# Pico2_W5_V1_0_20240830.net
KiCad netlist of a schematic drawn in EAGLE
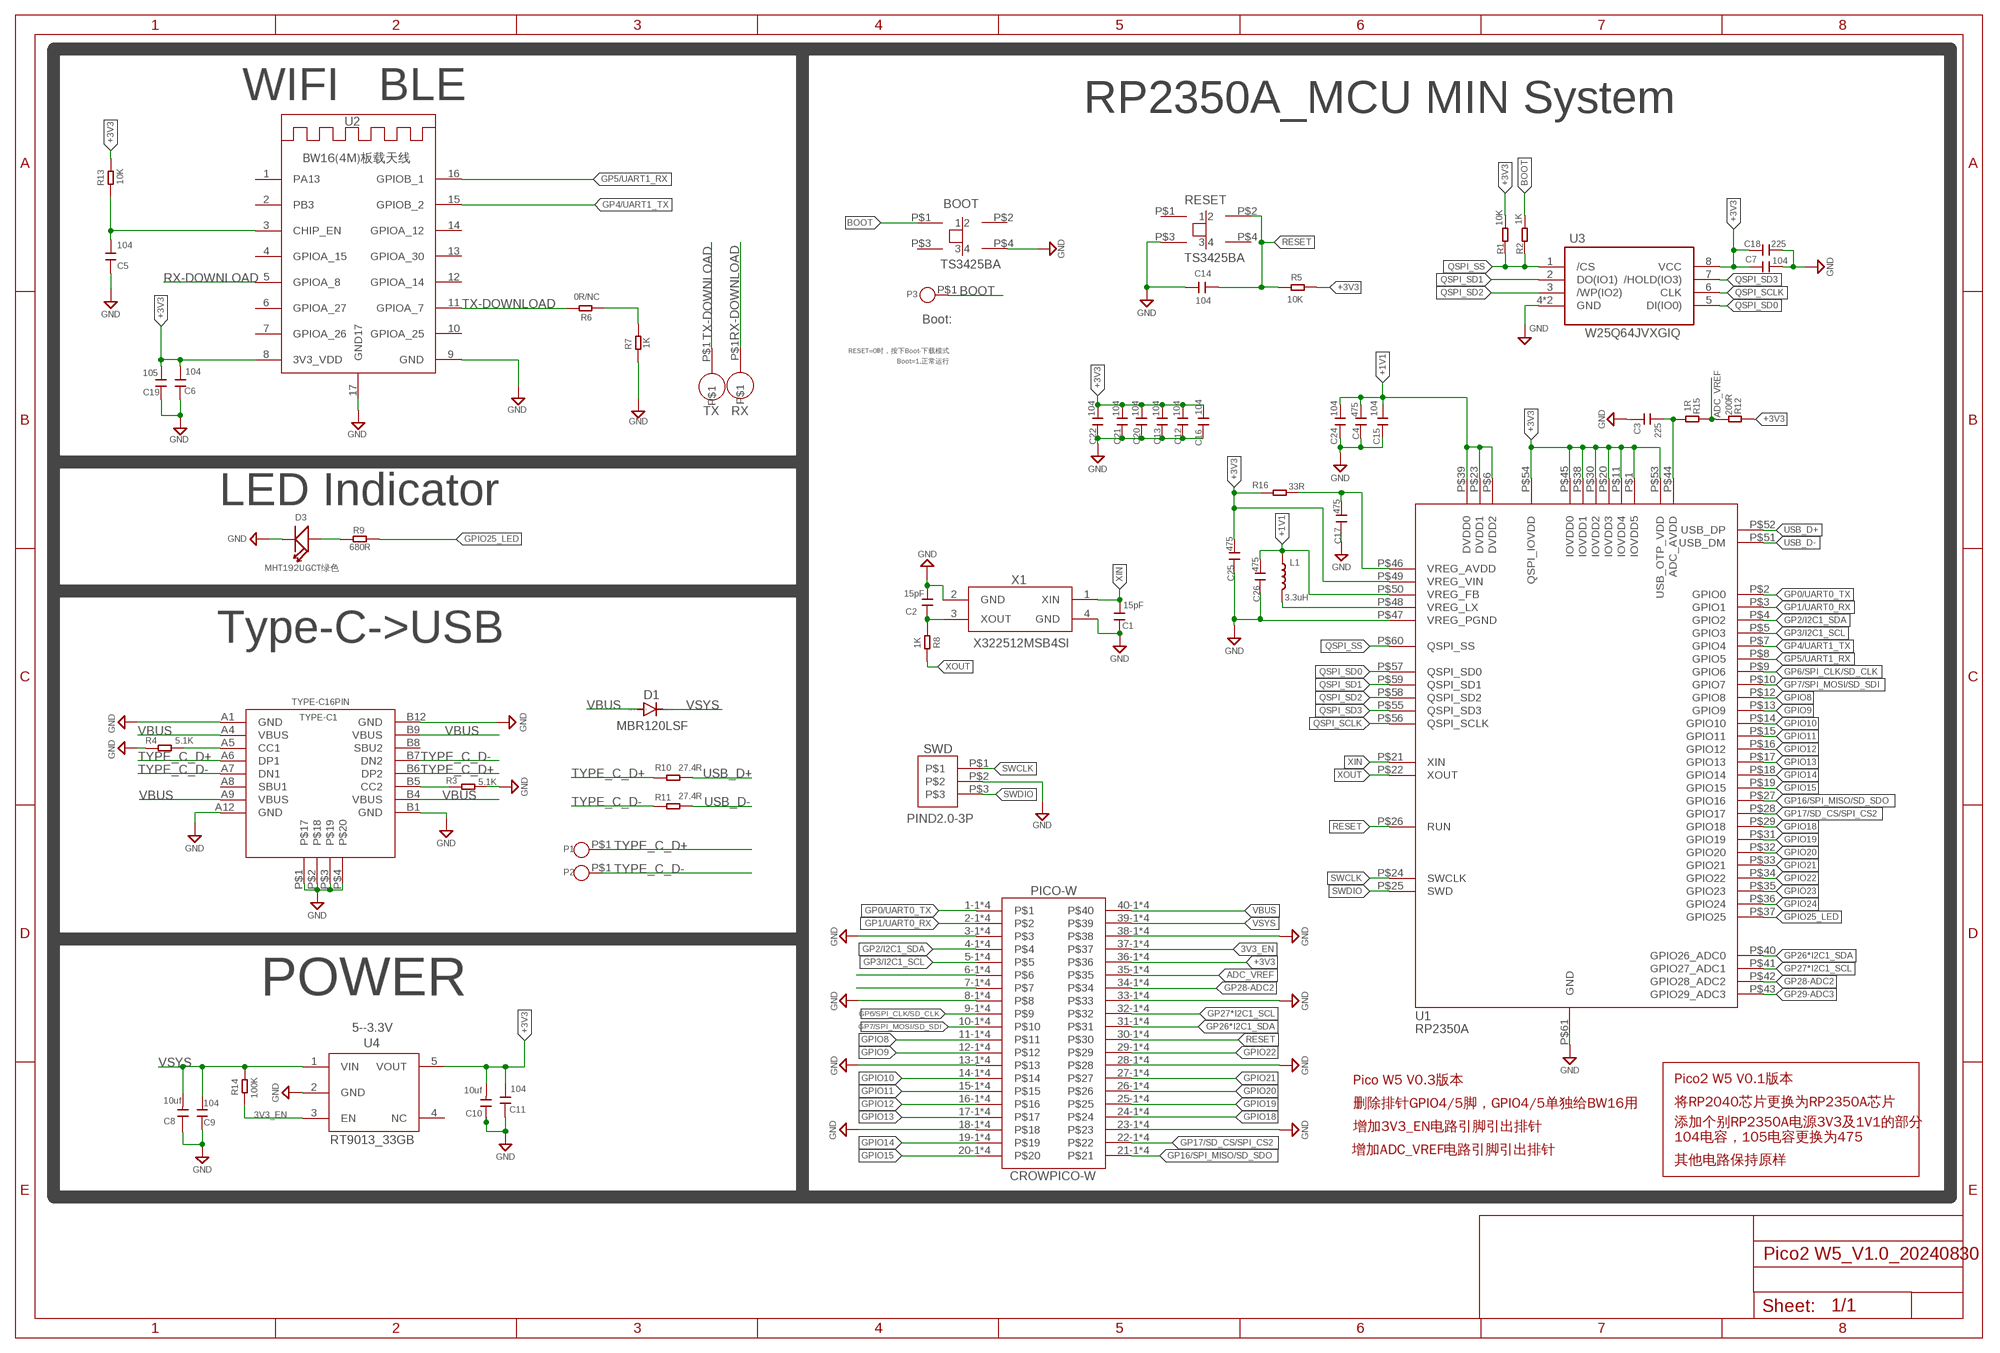
[diagram p0: schematic, sheet 1]

(export (version "E")
  (design (tool "Eeschema 10.0.6"))
  (components
    (comp (ref "BOOT")
      (value "TS3425BA")
      (footprint "eagle-import:SMD_KEY4.2_3._.2.5")
      (libsource (lib "eagle-import") (part "KEY"))
    )
    (comp (ref "C1")
      (value "15pF")
      (footprint "eagle-import:0201_W")
      (libsource (lib "eagle-import") (part "C0201"))
    )
    (comp (ref "C2")
      (value "15pF")
      (footprint "eagle-import:0201_W")
      (libsource (lib "eagle-import") (part "C0201"))
    )
    (comp (ref "C3")
      (value "225")
      (footprint "eagle-import:0201_W")
      (libsource (lib "eagle-import") (part "C0201"))
    )
    (comp (ref "C4")
      (value "475")
      (footprint "eagle-import:0201_W")
      (libsource (lib "eagle-import") (part "C0201"))
    )
    (comp (ref "C5")
      (value "104")
      (footprint "eagle-import:0201_W")
      (libsource (lib "eagle-import") (part "C0201"))
    )
    (comp (ref "C6")
      (value "104")
      (footprint "eagle-import:0201_W")
      (libsource (lib "eagle-import") (part "C0201"))
    )
    (comp (ref "C7")
      (value "104")
      (footprint "eagle-import:0201_W")
      (libsource (lib "eagle-import") (part "C0201"))
    )
    (comp (ref "C8")
      (value "10uf")
      (footprint "eagle-import:0402")
      (libsource (lib "eagle-import") (part "C0402"))
    )
    (comp (ref "C9")
      (value "104")
      (footprint "eagle-import:0201_W")
      (libsource (lib "eagle-import") (part "WGH_C0402"))
    )
    (comp (ref "C10")
      (value "10uf")
      (footprint "eagle-import:0402")
      (libsource (lib "eagle-import") (part "C0402"))
    )
    (comp (ref "C11")
      (value "104")
      (footprint "eagle-import:0201_W")
      (libsource (lib "eagle-import") (part "WGH_C0402"))
    )
    (comp (ref "C12")
      (value "104")
      (footprint "eagle-import:0201_W")
      (libsource (lib "eagle-import") (part "C0201"))
    )
    (comp (ref "C13")
      (value "104")
      (footprint "eagle-import:0201_W")
      (libsource (lib "eagle-import") (part "C0201"))
    )
    (comp (ref "C14")
      (value "104")
      (footprint "eagle-import:0201_W")
      (libsource (lib "eagle-import") (part "WGH_C0402"))
    )
    (comp (ref "C15")
      (value "104")
      (footprint "eagle-import:0201_W")
      (libsource (lib "eagle-import") (part "C0201"))
    )
    (comp (ref "C16")
      (value "104")
      (footprint "eagle-import:0201_W")
      (libsource (lib "eagle-import") (part "C0201"))
    )
    (comp (ref "C17")
      (value "475")
      (footprint "eagle-import:0201_W")
      (libsource (lib "eagle-import") (part "C0201"))
    )
    (comp (ref "C18")
      (value "225")
      (footprint "eagle-import:0201_W")
      (libsource (lib "eagle-import") (part "C0201"))
    )
    (comp (ref "C19")
      (value "105")
      (footprint "eagle-import:0201_W")
      (libsource (lib "eagle-import") (part "C0201"))
    )
    (comp (ref "C20")
      (value "104")
      (footprint "eagle-import:0201_W")
      (libsource (lib "eagle-import") (part "C0201"))
    )
    (comp (ref "C21")
      (value "104")
      (footprint "eagle-import:0201_W")
      (libsource (lib "eagle-import") (part "C0201"))
    )
    (comp (ref "C22")
      (value "104")
      (footprint "eagle-import:0201_W")
      (libsource (lib "eagle-import") (part "C0201"))
    )
    (comp (ref "C24")
      (value "104")
      (footprint "eagle-import:0201_W")
      (libsource (lib "eagle-import") (part "C0201"))
    )
    (comp (ref "C25")
      (value "475")
      (footprint "eagle-import:0201_W")
      (libsource (lib "eagle-import") (part "C0201"))
    )
    (comp (ref "C26")
      (value "475")
      (footprint "eagle-import:0201_W")
      (libsource (lib "eagle-import") (part "C0201"))
    )
    (comp (ref "D1")
      (value "MBR120LSF")
      (footprint "eagle-import:SOD123")
      (libsource (lib "eagle-import") (part "DIODE-SOD123"))
    )
    (comp (ref "D3")
      (value "MHT192UGCT绿色")
      (footprint "eagle-import:DISCRETE_D0603")
      (libsource (lib "eagle-import") (part "DISCRETE_007-LED0603"))
    )
    (comp (ref "L1")
      (value "3.3uH")
      (footprint "eagle-import:SMD,1.6X2MM")
      (libsource (lib "eagle-import") (part "FTC201610S3R3MBCA"))
    )
    (comp (ref "P1")
      (value "TP")
      (footprint "eagle-import:CROWPICO_W_PAD-1P")
      (libsource (lib "eagle-import") (part "CROWPICO_W_PAD-1P"))
    )
    (comp (ref "P2")
      (value "TP")
      (footprint "eagle-import:CROWPICO_W_PAD-1P")
      (libsource (lib "eagle-import") (part "CROWPICO_W_PAD-1P"))
    )
    (comp (ref "P3")
      (value "TP")
      (footprint "eagle-import:CROWPICO_W_PAD-1P")
      (libsource (lib "eagle-import") (part "CROWPICO_W_PAD-1P"))
    )
    (comp (ref "PICO-W")
      (value "CROWPICO-W")
      (footprint "eagle-import:CROWPICO-W")
      (libsource (lib "eagle-import") (part "CROWPICO-WCROWPICO-W1"))
    )
    (comp (ref "R1")
      (value "10K")
      (footprint "eagle-import:0201_W")
      (libsource (lib "eagle-import") (part "R0201"))
    )
    (comp (ref "R2")
      (value "1K")
      (footprint "eagle-import:0201_W")
      (libsource (lib "eagle-import") (part "R0201"))
    )
    (comp (ref "R3")
      (value "5.1K")
      (footprint "eagle-import:0201_W")
      (libsource (lib "eagle-import") (part "R0201"))
    )
    (comp (ref "R4")
      (value "5.1K")
      (footprint "eagle-import:0201_W")
      (libsource (lib "eagle-import") (part "R0201"))
    )
    (comp (ref "R5")
      (value "10K")
      (footprint "eagle-import:0201_W")
      (libsource (lib "eagle-import") (part "R0201"))
    )
    (comp (ref "R6")
      (value "0R/NC")
      (footprint "eagle-import:0201_W")
      (libsource (lib "eagle-import") (part "R0201"))
    )
    (comp (ref "R7")
      (value "1K")
      (footprint "eagle-import:0201_W")
      (libsource (lib "eagle-import") (part "R0201"))
    )
    (comp (ref "R8")
      (value "1K")
      (footprint "eagle-import:0201_W")
      (libsource (lib "eagle-import") (part "R0201"))
    )
    (comp (ref "R9")
      (value "680R")
      (footprint "eagle-import:0201_W")
      (libsource (lib "eagle-import") (part "R0201"))
    )
    (comp (ref "R10")
      (value "27.4R")
      (footprint "eagle-import:0201_W")
      (libsource (lib "eagle-import") (part "R0201"))
    )
    (comp (ref "R11")
      (value "27.4R")
      (footprint "eagle-import:0201_W")
      (libsource (lib "eagle-import") (part "R0201"))
    )
    (comp (ref "R12")
      (value "200R")
      (footprint "eagle-import:0201_W")
      (libsource (lib "eagle-import") (part "R0201"))
    )
    (comp (ref "R13")
      (value "10K")
      (footprint "eagle-import:0201_W")
      (libsource (lib "eagle-import") (part "R0201"))
    )
    (comp (ref "R14")
      (value "100K")
      (footprint "eagle-import:0201_W")
      (libsource (lib "eagle-import") (part "R0201"))
    )
    (comp (ref "R15")
      (value "1R")
      (footprint "eagle-import:0201_W")
      (libsource (lib "eagle-import") (part "R0201"))
    )
    (comp (ref "R16")
      (value "33R")
      (footprint "eagle-import:0201_W")
      (libsource (lib "eagle-import") (part "R0201"))
    )
    (comp (ref "RESET")
      (value "TS3425BA")
      (footprint "eagle-import:SMD_KEY4.2_3._.2.5")
      (libsource (lib "eagle-import") (part "KEY"))
    )
    (comp (ref "RX") (value "TP") (footprint "eagle-import:TP2") (libsource (lib "eagle-import") (part "TP")))
    (comp (ref "SWD")
      (value "PIND2.0-3P")
      (footprint "eagle-import:HDR2.0-3P")
      (libsource (lib "eagle-import") (part "PIND2.0"))
    )
    (comp (ref "TX") (value "TP") (footprint "eagle-import:TP2") (libsource (lib "eagle-import") (part "TP")))
    (comp (ref "TYPE-C1")
      (value "TYPE-C16PIN")
      (footprint "eagle-import:TYPE-C16PIN2MD(073)")
      (libsource (lib "eagle-import") (part "TYPE-C-16PIN"))
    )
    (comp (ref "U1")
      (value "RP2350A")
      (footprint "eagle-import:QFN-60_7X7MM")
      (libsource (lib "eagle-import") (part "RP2350A"))
    )
    (comp (ref "U2")
      (value "BW16(4M)板载天线")
      (footprint "eagle-import:BW16")
      (libsource (lib "eagle-import") (part "BW16"))
    )
    (comp (ref "U3")
      (value "W25Q64JVXGIQ")
      (footprint "eagle-import:W25QXX-XSON-8-EP(4X4)")
      (libsource (lib "eagle-import") (part "W25QXX"))
    )
    (comp (ref "U4")
      (value "RT9013_33GB")
      (footprint "eagle-import:SOT23-5_W")
      (libsource (lib "eagle-import") (part "RT9013"))
    )
    (comp (ref "X1")
      (value "X322512MSB4SI")
      (footprint "eagle-import:A_XBJ_SMD3225")
      (libsource (lib "eagle-import") (part "A_XBJ_XTAL"))
    )
  )
  (nets
    (net (code "1") (name "+1V1") (class "Default")
      (node (ref "C15") (pin "1") (pinfunction "1_1") (pintype "passive"))
      (node (ref "C24") (pin "1") (pinfunction "1_1") (pintype "passive"))
      (node (ref "C26") (pin "1") (pinfunction "1_1") (pintype "passive"))
      (node (ref "C4") (pin "1") (pinfunction "1_1") (pintype "passive"))
      (node (ref "L1") (pin "P$1") (pinfunction "1_P$1") (pintype "passive"))
      (node (ref "U1") (pin "P$23") (pinfunction "DVDD1_P$23") (pintype "power_in"))
      (node (ref "U1") (pin "P$39") (pinfunction "DVDD0_P$39") (pintype "power_in"))
      (node (ref "U1") (pin "P$50") (pinfunction "VREG_FB_P$50") (pintype "bidirectional"))
      (node (ref "U1") (pin "P$6") (pinfunction "DVDD2_P$6") (pintype "power_in"))
    )
    (net (code "2") (name "+3V3") (class "Default")
      (node (ref "C10") (pin "2") (pinfunction "2_2") (pintype "passive"))
      (node (ref "C11") (pin "2") (pinfunction "2_2") (pintype "passive"))
      (node (ref "C12") (pin "1") (pinfunction "1_1") (pintype "passive"))
      (node (ref "C13") (pin "1") (pinfunction "1_1") (pintype "passive"))
      (node (ref "C16") (pin "1") (pinfunction "1_1") (pintype "passive"))
      (node (ref "C18") (pin "1") (pinfunction "1_1") (pintype "passive"))
      (node (ref "C19") (pin "2") (pinfunction "2_2") (pintype "passive"))
      (node (ref "C20") (pin "1") (pinfunction "1_1") (pintype "passive"))
      (node (ref "C21") (pin "1") (pinfunction "1_1") (pintype "passive"))
      (node (ref "C22") (pin "1") (pinfunction "1_1") (pintype "passive"))
      (node (ref "C25") (pin "1") (pinfunction "1_1") (pintype "passive"))
      (node (ref "C6") (pin "2") (pinfunction "2_2") (pintype "passive"))
      (node (ref "C7") (pin "1") (pinfunction "1_1") (pintype "passive"))
      (node (ref "PICO-W") (pin "36-1") (pinfunction "P$36_36-1") (pintype "bidirectional"))
      (node (ref "PICO-W") (pin "36-2") (pinfunction "P$36_36-2") (pintype "bidirectional"))
      (node (ref "PICO-W") (pin "36-3") (pinfunction "P$36_36-3") (pintype "bidirectional"))
      (node (ref "PICO-W") (pin "36-4") (pinfunction "P$36_36-4") (pintype "bidirectional"))
      (node (ref "R1") (pin "2") (pinfunction "2_2") (pintype "passive"))
      (node (ref "R12") (pin "2") (pinfunction "2_2") (pintype "passive"))
      (node (ref "R13") (pin "2") (pinfunction "2_2") (pintype "passive"))
      (node (ref "R16") (pin "2") (pinfunction "2_2") (pintype "passive"))
      (node (ref "R5") (pin "2") (pinfunction "2_2") (pintype "passive"))
      (node (ref "U1") (pin "P$1") (pinfunction "IOVDD5_P$1") (pintype "power_in"))
      (node (ref "U1") (pin "P$11") (pinfunction "IOVDD4_P$11") (pintype "power_in"))
      (node (ref "U1") (pin "P$20") (pinfunction "IOVDD3_P$20") (pintype "power_in"))
      (node (ref "U1") (pin "P$30") (pinfunction "IOVDD2_P$30") (pintype "power_in"))
      (node (ref "U1") (pin "P$38") (pinfunction "IOVDD1_P$38") (pintype "power_in"))
      (node (ref "U1") (pin "P$45") (pinfunction "IOVDD0_P$45") (pintype "power_in"))
      (node (ref "U1") (pin "P$49") (pinfunction "VREG_VIN_P$49") (pintype "bidirectional"))
      (node (ref "U1") (pin "P$53") (pinfunction "USB_OTP_VDD_P$53") (pintype "power_in"))
      (node (ref "U1") (pin "P$54") (pinfunction "QSPI_IOVDD_P$54") (pintype "power_in"))
      (node (ref "U2") (pin "8") (pinfunction "3V3_VDD_8") (pintype "bidirectional"))
      (node (ref "U3") (pin "8") (pinfunction "VCC_8") (pintype "bidirectional"))
      (node (ref "U4") (pin "5") (pinfunction "VOUT_5") (pintype "bidirectional"))
    )
    (net (code "3") (name "/RX-DOWNLOAD") (class "Default")
      (node (ref "RX") (pin "P$1") (pinfunction "P$1_P$1") (pintype "bidirectional"))
      (node (ref "U2") (pin "5") (pinfunction "GPIOA_8_5") (pintype "bidirectional"))
    )
    (net (code "4") (name "/TX-DOWNLOAD") (class "Default")
      (node (ref "R6") (pin "2") (pinfunction "2_2") (pintype "passive"))
      (node (ref "TX") (pin "P$1") (pinfunction "P$1_P$1") (pintype "bidirectional"))
      (node (ref "U2") (pin "11") (pinfunction "GPIOA_7_11") (pintype "bidirectional"))
    )
    (net (code "5") (name "/TYPE_C_D+") (class "Default")
      (node (ref "P1") (pin "P$1") (pinfunction "P$1_P$1") (pintype "bidirectional"))
      (node (ref "R10") (pin "1") (pinfunction "1_1") (pintype "passive"))
      (node (ref "TYPE-C1") (pin "A6") (pinfunction "DP1_A6") (pintype "bidirectional"))
      (node (ref "TYPE-C1") (pin "B6") (pinfunction "DP2_B6") (pintype "bidirectional"))
    )
    (net (code "6") (name "/TYPE_C_D-") (class "Default")
      (node (ref "P2") (pin "P$1") (pinfunction "P$1_P$1") (pintype "bidirectional"))
      (node (ref "R11") (pin "1") (pinfunction "1_1") (pintype "passive"))
      (node (ref "TYPE-C1") (pin "A7") (pinfunction "DN1_A7") (pintype "bidirectional"))
      (node (ref "TYPE-C1") (pin "B7") (pinfunction "DN2_B7") (pintype "bidirectional"))
    )
    (net (code "7") (name "3V3_EN") (class "Default")
      (node (ref "PICO-W") (pin "37-1") (pinfunction "P$37_37-1") (pintype "bidirectional"))
      (node (ref "PICO-W") (pin "37-2") (pinfunction "P$37_37-2") (pintype "bidirectional"))
      (node (ref "PICO-W") (pin "37-3") (pinfunction "P$37_37-3") (pintype "bidirectional"))
      (node (ref "PICO-W") (pin "37-4") (pinfunction "P$37_37-4") (pintype "bidirectional"))
      (node (ref "R14") (pin "1") (pinfunction "1_1") (pintype "passive"))
      (node (ref "U4") (pin "3") (pinfunction "EN_3") (pintype "bidirectional"))
    )
    (net (code "8") (name "ADC_VREF") (class "Default")
      (node (ref "PICO-W") (pin "35-1") (pinfunction "P$35_35-1") (pintype "bidirectional"))
      (node (ref "PICO-W") (pin "35-2") (pinfunction "P$35_35-2") (pintype "bidirectional"))
      (node (ref "PICO-W") (pin "35-3") (pinfunction "P$35_35-3") (pintype "bidirectional"))
      (node (ref "PICO-W") (pin "35-4") (pinfunction "P$35_35-4") (pintype "bidirectional"))
      (node (ref "R12") (pin "1") (pinfunction "1_1") (pintype "passive"))
      (node (ref "R15") (pin "2") (pinfunction "2_2") (pintype "passive"))
    )
    (net (code "9") (name "BOOT") (class "Default")
      (node (ref "BOOT") (pin "P$1") (pinfunction "1_P$1") (pintype "bidirectional"))
      (node (ref "P3") (pin "P$1") (pinfunction "P$1_P$1") (pintype "bidirectional"))
      (node (ref "R2") (pin "2") (pinfunction "2_2") (pintype "passive"))
    )
    (net (code "10") (name "GND") (class "Default")
      (node (ref "BOOT") (pin "P$4") (pinfunction "4_P$4") (pintype "bidirectional"))
      (node (ref "C1") (pin "2") (pinfunction "2_2") (pintype "passive"))
      (node (ref "C10") (pin "1") (pinfunction "1_1") (pintype "passive"))
      (node (ref "C11") (pin "1") (pinfunction "1_1") (pintype "passive"))
      (node (ref "C12") (pin "2") (pinfunction "2_2") (pintype "passive"))
      (node (ref "C13") (pin "2") (pinfunction "2_2") (pintype "passive"))
      (node (ref "C14") (pin "1") (pinfunction "1_1") (pintype "passive"))
      (node (ref "C15") (pin "2") (pinfunction "2_2") (pintype "passive"))
      (node (ref "C16") (pin "2") (pinfunction "2_2") (pintype "passive"))
      (node (ref "C17") (pin "2") (pinfunction "2_2") (pintype "passive"))
      (node (ref "C18") (pin "2") (pinfunction "2_2") (pintype "passive"))
      (node (ref "C19") (pin "1") (pinfunction "1_1") (pintype "passive"))
      (node (ref "C2") (pin "1") (pinfunction "1_1") (pintype "passive"))
      (node (ref "C20") (pin "2") (pinfunction "2_2") (pintype "passive"))
      (node (ref "C21") (pin "2") (pinfunction "2_2") (pintype "passive"))
      (node (ref "C22") (pin "2") (pinfunction "2_2") (pintype "passive"))
      (node (ref "C24") (pin "2") (pinfunction "2_2") (pintype "passive"))
      (node (ref "C25") (pin "2") (pinfunction "2_2") (pintype "passive"))
      (node (ref "C26") (pin "2") (pinfunction "2_2") (pintype "passive"))
      (node (ref "C3") (pin "2") (pinfunction "2_2") (pintype "passive"))
      (node (ref "C4") (pin "2") (pinfunction "2_2") (pintype "passive"))
      (node (ref "C5") (pin "1") (pinfunction "1_1") (pintype "passive"))
      (node (ref "C6") (pin "1") (pinfunction "1_1") (pintype "passive"))
      (node (ref "C7") (pin "2") (pinfunction "2_2") (pintype "passive"))
      (node (ref "C8") (pin "1") (pinfunction "1_1") (pintype "passive"))
      (node (ref "C9") (pin "1") (pinfunction "1_1") (pintype "passive"))
      (node (ref "D3") (pin "-") (pinfunction "-_-") (pintype "passive"))
      (node (ref "PICO-W") (pin "13-1") (pinfunction "P$13_13-1") (pintype "bidirectional"))
      (node (ref "PICO-W") (pin "13-2") (pinfunction "P$13_13-2") (pintype "bidirectional"))
      (node (ref "PICO-W") (pin "13-3") (pinfunction "P$13_13-3") (pintype "bidirectional"))
      (node (ref "PICO-W") (pin "13-4") (pinfunction "P$13_13-4") (pintype "bidirectional"))
      (node (ref "PICO-W") (pin "18-1") (pinfunction "P$18_18-1") (pintype "bidirectional"))
      (node (ref "PICO-W") (pin "18-2") (pinfunction "P$18_18-2") (pintype "bidirectional"))
      (node (ref "PICO-W") (pin "18-3") (pinfunction "P$18_18-3") (pintype "bidirectional"))
      (node (ref "PICO-W") (pin "18-4") (pinfunction "P$18_18-4") (pintype "bidirectional"))
      (node (ref "PICO-W") (pin "23-1") (pinfunction "P$23_23-1") (pintype "bidirectional"))
      (node (ref "PICO-W") (pin "23-2") (pinfunction "P$23_23-2") (pintype "bidirectional"))
      (node (ref "PICO-W") (pin "23-3") (pinfunction "P$23_23-3") (pintype "bidirectional"))
      (node (ref "PICO-W") (pin "23-4") (pinfunction "P$23_23-4") (pintype "bidirectional"))
      (node (ref "PICO-W") (pin "28-1") (pinfunction "P$28_28-1") (pintype "bidirectional"))
      (node (ref "PICO-W") (pin "28-2") (pinfunction "P$28_28-2") (pintype "bidirectional"))
      (node (ref "PICO-W") (pin "28-3") (pinfunction "P$28_28-3") (pintype "bidirectional"))
      (node (ref "PICO-W") (pin "28-4") (pinfunction "P$28_28-4") (pintype "bidirectional"))
      (node (ref "PICO-W") (pin "3-1") (pinfunction "P$3_3-1") (pintype "bidirectional"))
      (node (ref "PICO-W") (pin "3-2") (pinfunction "P$3_3-2") (pintype "bidirectional"))
      (node (ref "PICO-W") (pin "3-3") (pinfunction "P$3_3-3") (pintype "bidirectional"))
      (node (ref "PICO-W") (pin "3-4") (pinfunction "P$3_3-4") (pintype "bidirectional"))
      (node (ref "PICO-W") (pin "33-1") (pinfunction "P$33_33-1") (pintype "bidirectional"))
      (node (ref "PICO-W") (pin "33-2") (pinfunction "P$33_33-2") (pintype "bidirectional"))
      (node (ref "PICO-W") (pin "33-3") (pinfunction "P$33_33-3") (pintype "bidirectional"))
      (node (ref "PICO-W") (pin "33-4") (pinfunction "P$33_33-4") (pintype "bidirectional"))
      (node (ref "PICO-W") (pin "38-1") (pinfunction "P$38_38-1") (pintype "bidirectional"))
      (node (ref "PICO-W") (pin "38-2") (pinfunction "P$38_38-2") (pintype "bidirectional"))
      (node (ref "PICO-W") (pin "38-3") (pinfunction "P$38_38-3") (pintype "bidirectional"))
      (node (ref "PICO-W") (pin "38-4") (pinfunction "P$38_38-4") (pintype "bidirectional"))
      (node (ref "PICO-W") (pin "8-1") (pinfunction "P$8_8-1") (pintype "bidirectional"))
      (node (ref "PICO-W") (pin "8-2") (pinfunction "P$8_8-2") (pintype "bidirectional"))
      (node (ref "PICO-W") (pin "8-3") (pinfunction "P$8_8-3") (pintype "bidirectional"))
      (node (ref "PICO-W") (pin "8-4") (pinfunction "P$8_8-4") (pintype "bidirectional"))
      (node (ref "R3") (pin "2") (pinfunction "2_2") (pintype "passive"))
      (node (ref "R4") (pin "1") (pinfunction "1_1") (pintype "passive"))
      (node (ref "R7") (pin "1") (pinfunction "1_1") (pintype "passive"))
      (node (ref "RESET") (pin "P$3") (pinfunction "3_P$3") (pintype "bidirectional"))
      (node (ref "SWD") (pin "P$2") (pinfunction "P$2_P$2") (pintype "bidirectional"))
      (node (ref "TYPE-C1") (pin "A1") (pinfunction "GND_A1") (pintype "bidirectional"))
      (node (ref "TYPE-C1") (pin "A12") (pinfunction "GND_A12") (pintype "bidirectional"))
      (node (ref "TYPE-C1") (pin "B1") (pinfunction "GND_B1") (pintype "bidirectional"))
      (node (ref "TYPE-C1") (pin "B12") (pinfunction "GND_B12") (pintype "bidirectional"))
      (node (ref "TYPE-C1") (pin "P$1") (pinfunction "P$17_P$1") (pintype "bidirectional"))
      (node (ref "TYPE-C1") (pin "P$2") (pinfunction "P$18_P$2") (pintype "bidirectional"))
      (node (ref "TYPE-C1") (pin "P$3") (pinfunction "P$19_P$3") (pintype "bidirectional"))
      (node (ref "TYPE-C1") (pin "P$4") (pinfunction "P$20_P$4") (pintype "bidirectional"))
      (node (ref "U1") (pin "P$47") (pinfunction "VREG_PGND_P$47") (pintype "bidirectional"))
      (node (ref "U1") (pin "P$61") (pinfunction "GND_P$61") (pintype "bidirectional"))
      (node (ref "U2") (pin "17") (pinfunction "GND17_17") (pintype "bidirectional"))
      (node (ref "U2") (pin "9") (pinfunction "GND_9") (pintype "bidirectional"))
      (node (ref "U3") (pin "4") (pinfunction "GND_4") (pintype "bidirectional"))
      (node (ref "U3") (pin "EP") (pinfunction "GND_EP") (pintype "bidirectional"))
      (node (ref "U4") (pin "2") (pinfunction "GND_2") (pintype "bidirectional"))
      (node (ref "X1") (pin "2") (pinfunction "GND_2") (pintype "bidirectional"))
      (node (ref "X1") (pin "4") (pinfunction "GND_4") (pintype "bidirectional"))
    )
    (net (code "11") (name "GP0{slash}UART0_TX") (class "Default")
      (node (ref "PICO-W") (pin "1-1") (pinfunction "P$1_1-1") (pintype "bidirectional"))
      (node (ref "PICO-W") (pin "1-2") (pinfunction "P$1_1-2") (pintype "bidirectional"))
      (node (ref "PICO-W") (pin "1-3") (pinfunction "P$1_1-3") (pintype "bidirectional"))
      (node (ref "PICO-W") (pin "1-4") (pinfunction "P$1_1-4") (pintype "bidirectional"))
      (node (ref "U1") (pin "P$2") (pinfunction "GPIO0_P$2") (pintype "bidirectional"))
    )
    (net (code "12") (name "GP1{slash}UART0_RX") (class "Default")
      (node (ref "PICO-W") (pin "2-1") (pinfunction "P$2_2-1") (pintype "bidirectional"))
      (node (ref "PICO-W") (pin "2-2") (pinfunction "P$2_2-2") (pintype "bidirectional"))
      (node (ref "PICO-W") (pin "2-3") (pinfunction "P$2_2-3") (pintype "bidirectional"))
      (node (ref "PICO-W") (pin "2-4") (pinfunction "P$2_2-4") (pintype "bidirectional"))
      (node (ref "U1") (pin "P$3") (pinfunction "GPIO1_P$3") (pintype "bidirectional"))
    )
    (net (code "13") (name "GP2{slash}I2C1_SDA") (class "Default")
      (node (ref "PICO-W") (pin "4-1") (pinfunction "P$4_4-1") (pintype "bidirectional"))
      (node (ref "PICO-W") (pin "4-2") (pinfunction "P$4_4-2") (pintype "bidirectional"))
      (node (ref "PICO-W") (pin "4-3") (pinfunction "P$4_4-3") (pintype "bidirectional"))
      (node (ref "PICO-W") (pin "4-4") (pinfunction "P$4_4-4") (pintype "bidirectional"))
      (node (ref "U1") (pin "P$4") (pinfunction "GPIO2_P$4") (pintype "bidirectional"))
    )
    (net (code "14") (name "GP3{slash}I2C1_SCL") (class "Default")
      (node (ref "PICO-W") (pin "5-1") (pinfunction "P$5_5-1") (pintype "bidirectional"))
      (node (ref "PICO-W") (pin "5-2") (pinfunction "P$5_5-2") (pintype "bidirectional"))
      (node (ref "PICO-W") (pin "5-3") (pinfunction "P$5_5-3") (pintype "bidirectional"))
      (node (ref "PICO-W") (pin "5-4") (pinfunction "P$5_5-4") (pintype "bidirectional"))
      (node (ref "U1") (pin "P$5") (pinfunction "GPIO3_P$5") (pintype "bidirectional"))
    )
    (net (code "15") (name "GP4{slash}UART1_TX") (class "Default")
      (node (ref "U1") (pin "P$7") (pinfunction "GPIO4_P$7") (pintype "bidirectional"))
      (node (ref "U2") (pin "15") (pinfunction "GPIOB_2_15") (pintype "bidirectional"))
    )
    (net (code "16") (name "GP5{slash}UART1_RX") (class "Default")
      (node (ref "U1") (pin "P$8") (pinfunction "GPIO5_P$8") (pintype "bidirectional"))
      (node (ref "U2") (pin "16") (pinfunction "GPIOB_1_16") (pintype "bidirectional"))
    )
    (net (code "17") (name "GP6{slash}SPI_CLK{slash}SD_CLK") (class "Default")
      (node (ref "PICO-W") (pin "9-1") (pinfunction "P$9_9-1") (pintype "bidirectional"))
      (node (ref "PICO-W") (pin "9-2") (pinfunction "P$9_9-2") (pintype "bidirectional"))
      (node (ref "PICO-W") (pin "9-3") (pinfunction "P$9_9-3") (pintype "bidirectional"))
      (node (ref "PICO-W") (pin "9-4") (pinfunction "P$9_9-4") (pintype "bidirectional"))
      (node (ref "U1") (pin "P$9") (pinfunction "GPIO6_P$9") (pintype "bidirectional"))
    )
    (net (code "18") (name "GP7{slash}SPI_MOSI{slash}SD_SDI") (class "Default")
      (node (ref "PICO-W") (pin "10-1") (pinfunction "P$10_10-1") (pintype "bidirectional"))
      (node (ref "PICO-W") (pin "10-2") (pinfunction "P$10_10-2") (pintype "bidirectional"))
      (node (ref "PICO-W") (pin "10-3") (pinfunction "P$10_10-3") (pintype "bidirectional"))
      (node (ref "PICO-W") (pin "10-4") (pinfunction "P$10_10-4") (pintype "bidirectional"))
      (node (ref "U1") (pin "P$10") (pinfunction "GPIO7_P$10") (pintype "bidirectional"))
    )
    (net (code "19") (name "GP16{slash}SPI_MISO{slash}SD_SDO") (class "Default")
      (node (ref "PICO-W") (pin "21-1") (pinfunction "P$21_21-1") (pintype "bidirectional"))
      (node (ref "PICO-W") (pin "21-2") (pinfunction "P$21_21-2") (pintype "bidirectional"))
      (node (ref "PICO-W") (pin "21-3") (pinfunction "P$21_21-3") (pintype "bidirectional"))
      (node (ref "PICO-W") (pin "21-4") (pinfunction "P$21_21-4") (pintype "bidirectional"))
      (node (ref "U1") (pin "P$27") (pinfunction "GPIO16_P$27") (pintype "bidirectional"))
    )
    (net (code "20") (name "GP17{slash}SD_CS{slash}SPI_CS2") (class "Default")
      (node (ref "PICO-W") (pin "22-1") (pinfunction "P$22_22-1") (pintype "bidirectional"))
      (node (ref "PICO-W") (pin "22-2") (pinfunction "P$22_22-2") (pintype "bidirectional"))
      (node (ref "PICO-W") (pin "22-3") (pinfunction "P$22_22-3") (pintype "bidirectional"))
      (node (ref "PICO-W") (pin "22-4") (pinfunction "P$22_22-4") (pintype "bidirectional"))
      (node (ref "U1") (pin "P$28") (pinfunction "GPIO17_P$28") (pintype "bidirectional"))
    )
    (net (code "21") (name "GP26*I2C1_SDA") (class "Default")
      (node (ref "PICO-W") (pin "31-1") (pinfunction "P$31_31-1") (pintype "bidirectional"))
      (node (ref "PICO-W") (pin "31-2") (pinfunction "P$31_31-2") (pintype "bidirectional"))
      (node (ref "PICO-W") (pin "31-3") (pinfunction "P$31_31-3") (pintype "bidirectional"))
      (node (ref "PICO-W") (pin "31-4") (pinfunction "P$31_31-4") (pintype "bidirectional"))
      (node (ref "U1") (pin "P$40") (pinfunction "GPIO26_ADC0_P$40") (pintype "bidirectional"))
    )
    (net (code "22") (name "GP27*I2C1_SCL") (class "Default")
      (node (ref "PICO-W") (pin "32-1") (pinfunction "P$32_32-1") (pintype "bidirectional"))
      (node (ref "PICO-W") (pin "32-2") (pinfunction "P$32_32-2") (pintype "bidirectional"))
      (node (ref "PICO-W") (pin "32-3") (pinfunction "P$32_32-3") (pintype "bidirectional"))
      (node (ref "PICO-W") (pin "32-4") (pinfunction "P$32_32-4") (pintype "bidirectional"))
      (node (ref "U1") (pin "P$41") (pinfunction "GPIO27_ADC1_P$41") (pintype "bidirectional"))
    )
    (net (code "23") (name "GP28-ADC2") (class "Default")
      (node (ref "PICO-W") (pin "34-1") (pinfunction "P$34_34-1") (pintype "bidirectional"))
      (node (ref "PICO-W") (pin "34-2") (pinfunction "P$34_34-2") (pintype "bidirectional"))
      (node (ref "PICO-W") (pin "34-3") (pinfunction "P$34_34-3") (pintype "bidirectional"))
      (node (ref "PICO-W") (pin "34-4") (pinfunction "P$34_34-4") (pintype "bidirectional"))
      (node (ref "U1") (pin "P$42") (pinfunction "GPIO28_ADC2_P$42") (pintype "bidirectional"))
    )
    (net (code "24") (name "GP29-ADC3") (class "Default")
      (node (ref "U1") (pin "P$43") (pinfunction "GPIO29_ADC3_P$43") (pintype "bidirectional"))
    )
    (net (code "25") (name "GPIO8") (class "Default")
      (node (ref "PICO-W") (pin "11-1") (pinfunction "P$11_11-1") (pintype "bidirectional"))
      (node (ref "PICO-W") (pin "11-2") (pinfunction "P$11_11-2") (pintype "bidirectional"))
      (node (ref "PICO-W") (pin "11-3") (pinfunction "P$11_11-3") (pintype "bidirectional"))
      (node (ref "PICO-W") (pin "11-4") (pinfunction "P$11_11-4") (pintype "bidirectional"))
      (node (ref "U1") (pin "P$12") (pinfunction "GPIO8_P$12") (pintype "bidirectional"))
    )
    (net (code "26") (name "GPIO9") (class "Default")
      (node (ref "PICO-W") (pin "12-1") (pinfunction "P$12_12-1") (pintype "bidirectional"))
      (node (ref "PICO-W") (pin "12-2") (pinfunction "P$12_12-2") (pintype "bidirectional"))
      (node (ref "PICO-W") (pin "12-3") (pinfunction "P$12_12-3") (pintype "bidirectional"))
      (node (ref "PICO-W") (pin "12-4") (pinfunction "P$12_12-4") (pintype "bidirectional"))
      (node (ref "U1") (pin "P$13") (pinfunction "GPIO9_P$13") (pintype "bidirectional"))
    )
    (net (code "27") (name "GPIO10") (class "Default")
      (node (ref "PICO-W") (pin "14-1") (pinfunction "P$14_14-1") (pintype "bidirectional"))
      (node (ref "PICO-W") (pin "14-2") (pinfunction "P$14_14-2") (pintype "bidirectional"))
      (node (ref "PICO-W") (pin "14-3") (pinfunction "P$14_14-3") (pintype "bidirectional"))
      (node (ref "PICO-W") (pin "14-4") (pinfunction "P$14_14-4") (pintype "bidirectional"))
      (node (ref "U1") (pin "P$14") (pinfunction "GPIO10_P$14") (pintype "bidirectional"))
    )
    (net (code "28") (name "GPIO11") (class "Default")
      (node (ref "PICO-W") (pin "15-1") (pinfunction "P$15_15-1") (pintype "bidirectional"))
      (node (ref "PICO-W") (pin "15-2") (pinfunction "P$15_15-2") (pintype "bidirectional"))
      (node (ref "PICO-W") (pin "15-3") (pinfunction "P$15_15-3") (pintype "bidirectional"))
      (node (ref "PICO-W") (pin "15-4") (pinfunction "P$15_15-4") (pintype "bidirectional"))
      (node (ref "U1") (pin "P$15") (pinfunction "GPIO11_P$15") (pintype "bidirectional"))
    )
    (net (code "29") (name "GPIO12") (class "Default")
      (node (ref "PICO-W") (pin "16-1") (pinfunction "P$16_16-1") (pintype "bidirectional"))
      (node (ref "PICO-W") (pin "16-2") (pinfunction "P$16_16-2") (pintype "bidirectional"))
      (node (ref "PICO-W") (pin "16-3") (pinfunction "P$16_16-3") (pintype "bidirectional"))
      (node (ref "PICO-W") (pin "16-4") (pinfunction "P$16_16-4") (pintype "bidirectional"))
      (node (ref "U1") (pin "P$16") (pinfunction "GPIO12_P$16") (pintype "bidirectional"))
    )
    (net (code "30") (name "GPIO13") (class "Default")
      (node (ref "PICO-W") (pin "17-1") (pinfunction "P$17_17-1") (pintype "bidirectional"))
      (node (ref "PICO-W") (pin "17-2") (pinfunction "P$17_17-2") (pintype "bidirectional"))
      (node (ref "PICO-W") (pin "17-3") (pinfunction "P$17_17-3") (pintype "bidirectional"))
      (node (ref "PICO-W") (pin "17-4") (pinfunction "P$17_17-4") (pintype "bidirectional"))
      (node (ref "U1") (pin "P$17") (pinfunction "GPIO13_P$17") (pintype "bidirectional"))
    )
    (net (code "31") (name "GPIO14") (class "Default")
      (node (ref "PICO-W") (pin "19-1") (pinfunction "P$19_19-1") (pintype "bidirectional"))
      (node (ref "PICO-W") (pin "19-2") (pinfunction "P$19_19-2") (pintype "bidirectional"))
      (node (ref "PICO-W") (pin "19-3") (pinfunction "P$19_19-3") (pintype "bidirectional"))
      (node (ref "PICO-W") (pin "19-4") (pinfunction "P$19_19-4") (pintype "bidirectional"))
      (node (ref "U1") (pin "P$18") (pinfunction "GPIO14_P$18") (pintype "bidirectional"))
    )
    (net (code "32") (name "GPIO15") (class "Default")
      (node (ref "PICO-W") (pin "20-1") (pinfunction "P$20_20-1") (pintype "bidirectional"))
      (node (ref "PICO-W") (pin "20-2") (pinfunction "P$20_20-2") (pintype "bidirectional"))
      (node (ref "PICO-W") (pin "20-3") (pinfunction "P$20_20-3") (pintype "bidirectional"))
      (node (ref "PICO-W") (pin "20-4") (pinfunction "P$20_20-4") (pintype "bidirectional"))
      (node (ref "U1") (pin "P$19") (pinfunction "GPIO15_P$19") (pintype "bidirectional"))
    )
    (net (code "33") (name "GPIO18") (class "Default")
      (node (ref "PICO-W") (pin "24-1") (pinfunction "P$24_24-1") (pintype "bidirectional"))
      (node (ref "PICO-W") (pin "24-2") (pinfunction "P$24_24-2") (pintype "bidirectional"))
      (node (ref "PICO-W") (pin "24-3") (pinfunction "P$24_24-3") (pintype "bidirectional"))
      (node (ref "PICO-W") (pin "24-4") (pinfunction "P$24_24-4") (pintype "bidirectional"))
      (node (ref "U1") (pin "P$29") (pinfunction "GPIO18_P$29") (pintype "bidirectional"))
    )
    (net (code "34") (name "GPIO19") (class "Default")
      (node (ref "PICO-W") (pin "25-1") (pinfunction "P$25_25-1") (pintype "bidirectional"))
      (node (ref "PICO-W") (pin "25-2") (pinfunction "P$25_25-2") (pintype "bidirectional"))
      (node (ref "PICO-W") (pin "25-3") (pinfunction "P$25_25-3") (pintype "bidirectional"))
      (node (ref "PICO-W") (pin "25-4") (pinfunction "P$25_25-4") (pintype "bidirectional"))
      (node (ref "U1") (pin "P$31") (pinfunction "GPIO19_P$31") (pintype "bidirectional"))
    )
    (net (code "35") (name "GPIO20") (class "Default")
      (node (ref "PICO-W") (pin "26-1") (pinfunction "P$26_26-1") (pintype "bidirectional"))
      (node (ref "PICO-W") (pin "26-2") (pinfunction "P$26_26-2") (pintype "bidirectional"))
      (node (ref "PICO-W") (pin "26-3") (pinfunction "P$26_26-3") (pintype "bidirectional"))
      (node (ref "PICO-W") (pin "26-4") (pinfunction "P$26_26-4") (pintype "bidirectional"))
      (node (ref "U1") (pin "P$32") (pinfunction "GPIO20_P$32") (pintype "bidirectional"))
    )
    (net (code "36") (name "GPIO21") (class "Default")
      (node (ref "PICO-W") (pin "27-1") (pinfunction "P$27_27-1") (pintype "bidirectional"))
      (node (ref "PICO-W") (pin "27-2") (pinfunction "P$27_27-2") (pintype "bidirectional"))
      (node (ref "PICO-W") (pin "27-3") (pinfunction "P$27_27-3") (pintype "bidirectional"))
      (node (ref "PICO-W") (pin "27-4") (pinfunction "P$27_27-4") (pintype "bidirectional"))
      (node (ref "U1") (pin "P$33") (pinfunction "GPIO21_P$33") (pintype "bidirectional"))
    )
    (net (code "37") (name "GPIO22") (class "Default")
      (node (ref "PICO-W") (pin "29-1") (pinfunction "P$29_29-1") (pintype "bidirectional"))
      (node (ref "PICO-W") (pin "29-2") (pinfunction "P$29_29-2") (pintype "bidirectional"))
      (node (ref "PICO-W") (pin "29-3") (pinfunction "P$29_29-3") (pintype "bidirectional"))
      (node (ref "PICO-W") (pin "29-4") (pinfunction "P$29_29-4") (pintype "bidirectional"))
      (node (ref "U1") (pin "P$34") (pinfunction "GPIO22_P$34") (pintype "bidirectional"))
    )
    (net (code "38") (name "GPIO23") (class "Default")
      (node (ref "U1") (pin "P$35") (pinfunction "GPIO23_P$35") (pintype "bidirectional"))
    )
    (net (code "39") (name "GPIO24") (class "Default")
      (node (ref "U1") (pin "P$36") (pinfunction "GPIO24_P$36") (pintype "bidirectional"))
    )
    (net (code "40") (name "GPIO25_LED") (class "Default")
      (node (ref "R9") (pin "2") (pinfunction "2_2") (pintype "passive"))
      (node (ref "U1") (pin "P$37") (pinfunction "GPIO25_P$37") (pintype "bidirectional"))
    )
    (net (code "41") (name "Net-(D3-Pad+)") (class "Default")
      (node (ref "D3") (pin "+") (pinfunction "+_+") (pintype "passive"))
      (node (ref "R9") (pin "1") (pinfunction "1_1") (pintype "passive"))
    )
    (net (code "42") (name "Net-(L1-2)") (class "Default")
      (node (ref "L1") (pin "P$2") (pinfunction "2_P$2") (pintype "passive"))
      (node (ref "U1") (pin "P$48") (pinfunction "VREG_LX_P$48") (pintype "bidirectional"))
    )
    (net (code "43") (name "Net-(PICO-W-P$6-Pad6-1)") (class "Default")
      (node (ref "PICO-W") (pin "6-1") (pinfunction "P$6_6-1") (pintype "bidirectional"))
      (node (ref "PICO-W") (pin "6-2") (pinfunction "P$6_6-2") (pintype "bidirectional"))
      (node (ref "PICO-W") (pin "6-3") (pinfunction "P$6_6-3") (pintype "bidirectional"))
      (node (ref "PICO-W") (pin "6-4") (pinfunction "P$6_6-4") (pintype "bidirectional"))
    )
    (net (code "44") (name "Net-(PICO-W-P$7-Pad7-1)") (class "Default")
      (node (ref "PICO-W") (pin "7-1") (pinfunction "P$7_7-1") (pintype "bidirectional"))
      (node (ref "PICO-W") (pin "7-2") (pinfunction "P$7_7-2") (pintype "bidirectional"))
      (node (ref "PICO-W") (pin "7-3") (pinfunction "P$7_7-3") (pintype "bidirectional"))
      (node (ref "PICO-W") (pin "7-4") (pinfunction "P$7_7-4") (pintype "bidirectional"))
    )
    (net (code "45") (name "Net-(R6-Pad1)") (class "Default")
      (node (ref "R6") (pin "1") (pinfunction "1_1") (pintype "passive"))
      (node (ref "R7") (pin "2") (pinfunction "2_2") (pintype "passive"))
    )
    (net (code "46") (name "Net-(TYPE-C1-CC1)") (class "Default")
      (node (ref "R4") (pin "2") (pinfunction "2_2") (pintype "passive"))
      (node (ref "TYPE-C1") (pin "A5") (pinfunction "CC1_A5") (pintype "bidirectional"))
    )
    (net (code "47") (name "Net-(TYPE-C1-CC2)") (class "Default")
      (node (ref "R3") (pin "1") (pinfunction "1_1") (pintype "passive"))
      (node (ref "TYPE-C1") (pin "B5") (pinfunction "CC2_B5") (pintype "bidirectional"))
    )
    (net (code "48") (name "Net-(U1-ADC_AVDD)") (class "Default")
      (node (ref "C3") (pin "1") (pinfunction "1_1") (pintype "passive"))
      (node (ref "R15") (pin "1") (pinfunction "1_1") (pintype "passive"))
      (node (ref "U1") (pin "P$44") (pinfunction "ADC_AVDD_P$44") (pintype "power_in"))
    )
    (net (code "49") (name "Net-(U1-VREG_AVDD)") (class "Default")
      (node (ref "C17") (pin "1") (pinfunction "1_1") (pintype "passive"))
      (node (ref "R16") (pin "1") (pinfunction "1_1") (pintype "passive"))
      (node (ref "U1") (pin "P$46") (pinfunction "VREG_AVDD_P$46") (pintype "bidirectional"))
    )
    (net (code "50") (name "Net-(U2-CHIP_EN)") (class "Default")
      (node (ref "C5") (pin "2") (pinfunction "2_2") (pintype "passive"))
      (node (ref "R13") (pin "1") (pinfunction "1_1") (pintype "passive"))
      (node (ref "U2") (pin "3") (pinfunction "CHIP_EN_3") (pintype "bidirectional"))
    )
    (net (code "51") (name "Net-(X1-XOUT)") (class "Default")
      (node (ref "C2") (pin "2") (pinfunction "2_2") (pintype "passive"))
      (node (ref "R8") (pin "1") (pinfunction "1_1") (pintype "passive"))
      (node (ref "X1") (pin "3") (pinfunction "XOUT_3") (pintype "bidirectional"))
    )
    (net (code "52") (name "QSPI_SCLK") (class "Default")
      (node (ref "U1") (pin "P$56") (pinfunction "QSPI_SCLK_P$56") (pintype "bidirectional"))
      (node (ref "U3") (pin "6") (pinfunction "CLK_6") (pintype "bidirectional"))
    )
    (net (code "53") (name "QSPI_SD0") (class "Default")
      (node (ref "U1") (pin "P$57") (pinfunction "QSPI_SD0_P$57") (pintype "bidirectional"))
      (node (ref "U3") (pin "5") (pinfunction "DI(IO0)_5") (pintype "bidirectional"))
    )
    (net (code "54") (name "QSPI_SD1") (class "Default")
      (node (ref "U1") (pin "P$59") (pinfunction "QSPI_SD1_P$59") (pintype "bidirectional"))
      (node (ref "U3") (pin "2") (pinfunction "DO(IO1)_2") (pintype "bidirectional"))
    )
    (net (code "55") (name "QSPI_SD2") (class "Default")
      (node (ref "U1") (pin "P$58") (pinfunction "QSPI_SD2_P$58") (pintype "bidirectional"))
      (node (ref "U3") (pin "3") (pinfunction "/WP(IO2)_3") (pintype "bidirectional"))
    )
    (net (code "56") (name "QSPI_SD3") (class "Default")
      (node (ref "U1") (pin "P$55") (pinfunction "QSPI_SD3_P$55") (pintype "bidirectional"))
      (node (ref "U3") (pin "7") (pinfunction "/HOLD(IO3)_7") (pintype "bidirectional"))
    )
    (net (code "57") (name "QSPI_SS") (class "Default")
      (node (ref "R1") (pin "1") (pinfunction "1_1") (pintype "passive"))
      (node (ref "R2") (pin "1") (pinfunction "1_1") (pintype "passive"))
      (node (ref "U1") (pin "P$60") (pinfunction "QSPI_SS_P$60") (pintype "bidirectional"))
      (node (ref "U3") (pin "1") (pinfunction "/CS_1") (pintype "bidirectional"))
    )
    (net (code "58") (name "RESET") (class "Default")
      (node (ref "C14") (pin "2") (pinfunction "2_2") (pintype "passive"))
      (node (ref "PICO-W") (pin "30-1") (pinfunction "P$30_30-1") (pintype "bidirectional"))
      (node (ref "PICO-W") (pin "30-2") (pinfunction "P$30_30-2") (pintype "bidirectional"))
      (node (ref "PICO-W") (pin "30-3") (pinfunction "P$30_30-3") (pintype "bidirectional"))
      (node (ref "PICO-W") (pin "30-4") (pinfunction "P$30_30-4") (pintype "bidirectional"))
      (node (ref "R5") (pin "1") (pinfunction "1_1") (pintype "passive"))
      (node (ref "RESET") (pin "P$2") (pinfunction "2_P$2") (pintype "bidirectional"))
      (node (ref "U1") (pin "P$26") (pinfunction "RUN_P$26") (pintype "bidirectional"))
    )
    (net (code "59") (name "SWCLK") (class "Default")
      (node (ref "SWD") (pin "P$1") (pinfunction "P$1_P$1") (pintype "bidirectional"))
      (node (ref "U1") (pin "P$24") (pinfunction "SWCLK_P$24") (pintype "bidirectional"))
    )
    (net (code "60") (name "SWDIO") (class "Default")
      (node (ref "SWD") (pin "P$3") (pinfunction "P$3_P$3") (pintype "bidirectional"))
      (node (ref "U1") (pin "P$25") (pinfunction "SWD_P$25") (pintype "bidirectional"))
    )
    (net (code "61") (name "USB_D+") (class "Default")
      (node (ref "R10") (pin "2") (pinfunction "2_2") (pintype "passive"))
      (node (ref "U1") (pin "P$52") (pinfunction "USB_DP_P$52") (pintype "bidirectional"))
    )
    (net (code "62") (name "USB_D-") (class "Default")
      (node (ref "R11") (pin "2") (pinfunction "2_2") (pintype "passive"))
      (node (ref "U1") (pin "P$51") (pinfunction "USB_DM_P$51") (pintype "bidirectional"))
    )
    (net (code "63") (name "VBUS") (class "Default")
      (node (ref "D1") (pin "A") (pinfunction "A_A") (pintype "passive"))
      (node (ref "PICO-W") (pin "40-1") (pinfunction "P$40_40-1") (pintype "bidirectional"))
      (node (ref "PICO-W") (pin "40-2") (pinfunction "P$40_40-2") (pintype "bidirectional"))
      (node (ref "PICO-W") (pin "40-3") (pinfunction "P$40_40-3") (pintype "bidirectional"))
      (node (ref "PICO-W") (pin "40-4") (pinfunction "P$40_40-4") (pintype "bidirectional"))
      (node (ref "TYPE-C1") (pin "A4") (pinfunction "VBUS_A4") (pintype "bidirectional"))
      (node (ref "TYPE-C1") (pin "A9") (pinfunction "VBUS_A9") (pintype "bidirectional"))
      (node (ref "TYPE-C1") (pin "B4") (pinfunction "VBUS_B4") (pintype "bidirectional"))
      (node (ref "TYPE-C1") (pin "B9") (pinfunction "VBUS_B9") (pintype "bidirectional"))
    )
    (net (code "64") (name "VSYS") (class "Default")
      (node (ref "C8") (pin "2") (pinfunction "2_2") (pintype "passive"))
      (node (ref "C9") (pin "2") (pinfunction "2_2") (pintype "passive"))
      (node (ref "D1") (pin "C") (pinfunction "C_C") (pintype "passive"))
      (node (ref "PICO-W") (pin "39-1") (pinfunction "P$39_39-1") (pintype "bidirectional"))
      (node (ref "PICO-W") (pin "39-2") (pinfunction "P$39_39-2") (pintype "bidirectional"))
      (node (ref "PICO-W") (pin "39-3") (pinfunction "P$39_39-3") (pintype "bidirectional"))
      (node (ref "PICO-W") (pin "39-4") (pinfunction "P$39_39-4") (pintype "bidirectional"))
      (node (ref "R14") (pin "2") (pinfunction "2_2") (pintype "passive"))
      (node (ref "U4") (pin "1") (pinfunction "VIN_1") (pintype "bidirectional"))
    )
    (net (code "65") (name "XIN") (class "Default")
      (node (ref "C1") (pin "1") (pinfunction "1_1") (pintype "passive"))
      (node (ref "U1") (pin "P$21") (pinfunction "XIN_P$21") (pintype "bidirectional"))
      (node (ref "X1") (pin "1") (pinfunction "XIN_1") (pintype "bidirectional"))
    )
    (net (code "66") (name "XOUT") (class "Default")
      (node (ref "R8") (pin "2") (pinfunction "2_2") (pintype "passive"))
      (node (ref "U1") (pin "P$22") (pinfunction "XOUT_P$22") (pintype "bidirectional"))
    )
    (net (code "67") (name "unconnected-(BOOT-2-PadP$2)") (class "Default")
      (node (ref "BOOT") (pin "P$2") (pinfunction "2_P$2") (pintype "bidirectional"))
    )
    (net (code "68") (name "unconnected-(BOOT-3-PadP$3)") (class "Default")
      (node (ref "BOOT") (pin "P$3") (pinfunction "3_P$3") (pintype "bidirectional"))
    )
    (net (code "69") (name "unconnected-(RESET-1-PadP$1)") (class "Default")
      (node (ref "RESET") (pin "P$1") (pinfunction "1_P$1") (pintype "bidirectional"))
    )
    (net (code "70") (name "unconnected-(RESET-4-PadP$4)") (class "Default")
      (node (ref "RESET") (pin "P$4") (pinfunction "4_P$4") (pintype "bidirectional"))
    )
    (net (code "71") (name "unconnected-(TYPE-C1-SBU1-PadA8)") (class "Default")
      (node (ref "TYPE-C1") (pin "A8") (pinfunction "SBU1_A8") (pintype "bidirectional"))
    )
    (net (code "72") (name "unconnected-(TYPE-C1-SBU2-PadB8)") (class "Default")
      (node (ref "TYPE-C1") (pin "B8") (pinfunction "SBU2_B8") (pintype "bidirectional"))
    )
    (net (code "73") (name "unconnected-(U2-GPIOA_12-Pad14)") (class "Default")
      (node (ref "U2") (pin "14") (pinfunction "GPIOA_12_14") (pintype "bidirectional"))
    )
    (net (code "74") (name "unconnected-(U2-GPIOA_14-Pad12)") (class "Default")
      (node (ref "U2") (pin "12") (pinfunction "GPIOA_14_12") (pintype "bidirectional"))
    )
    (net (code "75") (name "unconnected-(U2-GPIOA_15-Pad4)") (class "Default")
      (node (ref "U2") (pin "4") (pinfunction "GPIOA_15_4") (pintype "bidirectional"))
    )
    (net (code "76") (name "unconnected-(U2-GPIOA_25-Pad10)") (class "Default")
      (node (ref "U2") (pin "10") (pinfunction "GPIOA_25_10") (pintype "bidirectional"))
    )
    (net (code "77") (name "unconnected-(U2-GPIOA_26-Pad7)") (class "Default")
      (node (ref "U2") (pin "7") (pinfunction "GPIOA_26_7") (pintype "bidirectional"))
    )
    (net (code "78") (name "unconnected-(U2-GPIOA_27-Pad6)") (class "Default")
      (node (ref "U2") (pin "6") (pinfunction "GPIOA_27_6") (pintype "bidirectional"))
    )
    (net (code "79") (name "unconnected-(U2-GPIOA_30-Pad13)") (class "Default")
      (node (ref "U2") (pin "13") (pinfunction "GPIOA_30_13") (pintype "bidirectional"))
    )
    (net (code "80") (name "unconnected-(U2-PA13-Pad1)") (class "Default")
      (node (ref "U2") (pin "1") (pinfunction "PA13_1") (pintype "bidirectional"))
    )
    (net (code "81") (name "unconnected-(U2-PB3-Pad2)") (class "Default")
      (node (ref "U2") (pin "2") (pinfunction "PB3_2") (pintype "bidirectional"))
    )
    (net (code "82") (name "unconnected-(U4-NC-Pad4)") (class "Default")
      (node (ref "U4") (pin "4") (pinfunction "NC_4") (pintype "bidirectional"))
    )
  )
)
